# power.net
KiCad netlist of a schematic drawn in Altium Designer
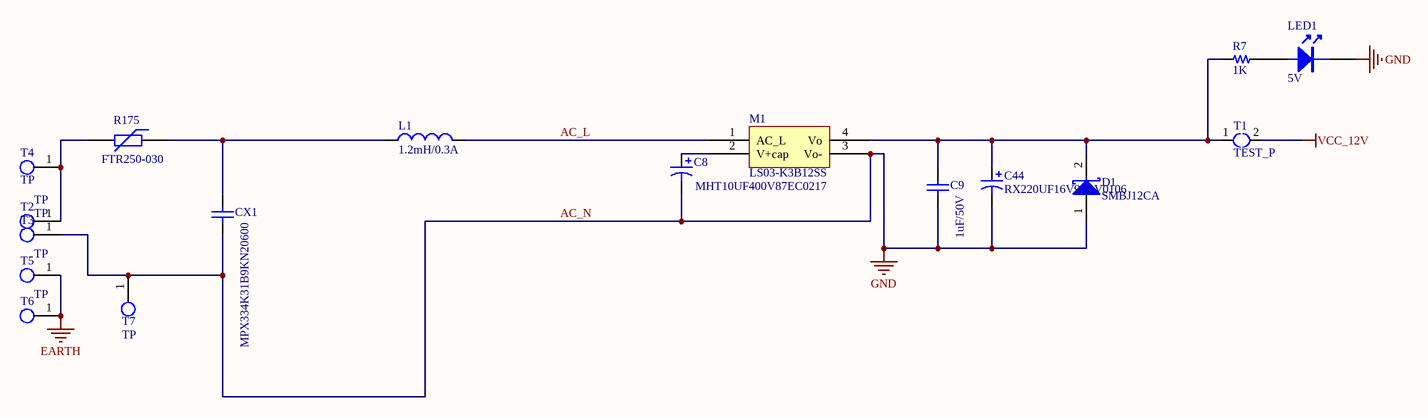
[diagram p0: power.SchDoc]

(export (version "E")
  (design (tool "Eeschema 10.0.6"))
  (components
    (comp (ref "C8")
      (value "MHT10UF400V87EC0217")
      (footprint "CAP-TH_BD6.3-P2.50-D0.5-FD")
      (description "Polarized Capacitor (Radial)")
      (fields (field (name "PUBLISHER") "Altium Limited"))
      (libsource (lib "Miscellaneous Devices") (part "Cap Pol1"))
    )
    (comp (ref "C9")
      (value "1uF/50V")
      (footprint "1206C")
      (description "Capacitor")
      (fields (field (name "PUBLISHER") "Altium Limited"))
      (libsource (lib "Miscellaneous Devices") (part "Cap"))
    )
    (comp (ref "C44")
      (value "RX220UF16V90RV0106")
      (footprint "CAP-SMD_BD6.3-L6.6-W6.6-FD-2")
      (description "Polarized Capacitor (Radial)")
      (fields (field (name "PUBLISHER") "Altium Limited"))
      (libsource (lib "Miscellaneous Devices") (part "Cap Pol1"))
    )
    (comp (ref "CX1")
      (value "MPX334K31B9KN20600")
      (footprint "CAP-TH_L10.0-W6.0-P7.50-D0.6")
      (description "Capacitor")
      (fields (field (name "PUBLISHER") "Altium Limited"))
      (libsource (lib "Miscellaneous Devices") (part "Cap"))
    )
    (comp (ref "D1")
      (value "SMBJ12CA")
      (footprint "SMB")
      (fields (field (name "PARTNUMBER") "1N5819HW-7-F") (field (name "MANUFACTURER") "Diodes Inc"))
      (libsource (lib "Bogen") (part "1N5819HW-7-F"))
    )
    (comp (ref "L1")
      (value "1.2mH/0.3A")
      (footprint "IND-TH_BD7.5-P3.00-D0.6")
      (description "Metal alloy Power Inductor, 10 uH, ±20%, 1210 (3225)")
      (fields (field (name "MANUFACTURER") "Murata") (field (name "PARTNUMBER") "1276AS-H-100M=P2"))
      (libsource (lib "Bogen") (part "1276AS-H-100M=P2"))
    )
    (comp (ref "LED1") (value "5V") (footprint "0603LED") (libsource (lib "*") (part "LED")))
    (comp (ref "M1") (value "LS03-K3B12SS") (libsource (lib "Schlib_20110825") (part "LS03-K3B12SS")))
    (comp (ref "R7") (value "1K") (footprint "0603R") (description "R") (libsource (lib "JRJ_1") (part "R")))
    (comp (ref "R175")
      (value "FTR250-030")
      (footprint "FUSE-TH_L6.0-W4.6-P5.10-D0.6-S4.00")
      (description "Varistor (Voltage-Sensitive Resistor)")
      (fields (field (name "PUBLISHER") "Altium Limited"))
      (libsource (lib "Miscellaneous Devices") (part "Res Varistor"))
    )
    (comp (ref "T1")
      (value "TEST_P")
      (footprint "TEST_P")
      (libsource (lib "Schlib_20110825") (part "TEST_P"))
    )
    (comp (ref "T2") (value "TP") (footprint "220V_Hole") (libsource (lib "Schlib_20110825") (part "TP")))
    (comp (ref "T3") (value "TP") (footprint "220V_Hole") (libsource (lib "Schlib_20110825") (part "TP")))
    (comp (ref "T4") (value "TP") (footprint "220V_Hole2") (libsource (lib "Schlib_20110825") (part "TP")))
    (comp (ref "T5") (value "TP") (footprint "220V_Hole") (libsource (lib "Schlib_20110825") (part "TP")))
    (comp (ref "T6") (value "TP") (footprint "220V_Hole2") (libsource (lib "Schlib_20110825") (part "TP")))
    (comp (ref "T7") (value "TP") (footprint "220V_Hole2") (libsource (lib "Schlib_20110825") (part "TP")))
  )
  (nets
    (net (code "1") (name "/AC_L") (class "Default")
      (node (ref "L1") (pin "2") (pinfunction "2_2") (pintype "passive"))
      (node (ref "M1") (pin "1") (pinfunction "AC_L_1") (pintype "passive"))
    )
    (net (code "2") (name "EARTH") (class "Default")
      (node (ref "T5") (pin "1") (pintype "passive"))
      (node (ref "T6") (pin "1") (pintype "passive"))
    )
    (net (code "3") (name "GND") (class "Default")
      (node (ref "C44") (pin "2") (pinfunction "2_2") (pintype "passive"))
      (node (ref "C8") (pin "2") (pinfunction "2_2") (pintype "passive"))
      (node (ref "C9") (pin "1") (pinfunction "1_1") (pintype "passive"))
      (node (ref "CX1") (pin "1") (pinfunction "1_1") (pintype "passive"))
      (node (ref "D1") (pin "1") (pinfunction "A_1") (pintype "passive"))
      (node (ref "LED1") (pin "2") (pinfunction "2_2") (pintype "passive"))
      (node (ref "M1") (pin "3") (pinfunction "Vo-_3") (pintype "passive"))
      (node (ref "T3") (pin "1") (pintype "passive"))
      (node (ref "T7") (pin "1") (pintype "passive"))
    )
    (net (code "4") (name "Net-(CX1-Pad2)") (class "Default")
      (node (ref "CX1") (pin "2") (pinfunction "2_2") (pintype "passive"))
      (node (ref "L1") (pin "1") (pinfunction "1_1") (pintype "passive"))
      (node (ref "R175") (pin "1") (pinfunction "1_1") (pintype "passive"))
    )
    (net (code "5") (name "Net-(D1-K)") (class "Default")
      (node (ref "C44") (pin "1") (pinfunction "1_1") (pintype "passive"))
      (node (ref "C9") (pin "2") (pinfunction "2_2") (pintype "passive"))
      (node (ref "D1") (pin "2") (pinfunction "K_2") (pintype "passive"))
      (node (ref "M1") (pin "4") (pinfunction "Vo_4") (pintype "passive"))
      (node (ref "R7") (pin "2") (pintype "passive"))
      (node (ref "T1") (pin "1") (pinfunction "1_1") (pintype "passive"))
    )
    (net (code "6") (name "Net-(LED1-Pad1)") (class "Default")
      (node (ref "LED1") (pin "1") (pinfunction "1_1") (pintype "passive"))
      (node (ref "R7") (pin "1") (pintype "passive"))
    )
    (net (code "7") (name "Net-(M1-V+cap)") (class "Default")
      (node (ref "C8") (pin "1") (pinfunction "1_1") (pintype "passive"))
      (node (ref "M1") (pin "2") (pinfunction "V+cap_2") (pintype "passive"))
    )
    (net (code "8") (name "Net-(R175-Pad2)") (class "Default")
      (node (ref "R175") (pin "2") (pinfunction "2_2") (pintype "passive"))
      (node (ref "T2") (pin "1") (pintype "passive"))
      (node (ref "T4") (pin "1") (pintype "passive"))
    )
    (net (code "9") (name "VCC_12V") (class "Default")
      (node (ref "T1") (pin "2") (pinfunction "2_2") (pintype "passive"))
    )
  )
)
